# M3406-Board_Match.net
KiCad netlist of a schematic drawn in Altium Designer
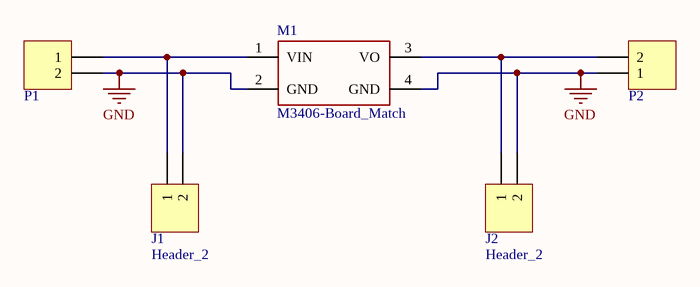
[diagram p0: M3406-Board_Match.SchDoc]

(export (version "E")
  (design (tool "Eeschema 10.0.6"))
  (components
    (comp (ref "J1")
      (value "Header_2")
      (footprint "HDR-TH_2P-P2.54-V-M-1")
      (description "直插,P=2.54mm")
      (libsource (lib "") (part "Header_2_1"))
    )
    (comp (ref "J2")
      (value "Header_2")
      (footprint "HDR-TH_2P-P2.54-V-M-1")
      (description "直插,P=2.54mm")
      (libsource (lib "") (part "Header_2_1"))
    )
    (comp (ref "M1")
      (value "M3406-Board_Match")
      (footprint "M3406-Board_Match")
      (description "M3406匹配板")
      (libsource (lib "std_lib") (part "M3406-Board_Match"))
    )
    (comp (ref "P1")
      (value "KF301-5")
      (footprint "TH_P5.00_KF301-5.0-2P")
      (description "直插,P=2.54mm")
      (libsource (lib "std_lib") (part "Header_2"))
    )
    (comp (ref "P2")
      (value "KF301-5")
      (footprint "TH_P5.00_KF301-5.0-2P")
      (description "直插,P=2.54mm")
      (libsource (lib "") (part "Header_2_2"))
    )
  )
  (nets
    (net (code "1") (name "GND") (class "Default")
      (node (ref "J1") (pin "2") (pinfunction "2_2") (pintype "passive"))
      (node (ref "J2") (pin "2") (pinfunction "2_2") (pintype "passive"))
      (node (ref "M1") (pin "2") (pinfunction "GND_2") (pintype "passive"))
      (node (ref "M1") (pin "4") (pinfunction "GND_4") (pintype "passive"))
      (node (ref "P1") (pin "2") (pinfunction "2_2") (pintype "passive"))
      (node (ref "P2") (pin "1") (pinfunction "1_1") (pintype "passive"))
    )
    (net (code "2") (name "Net-(M1-VIN)") (class "Default")
      (node (ref "J1") (pin "1") (pinfunction "1_1") (pintype "passive"))
      (node (ref "M1") (pin "1") (pinfunction "VIN_1") (pintype "passive"))
      (node (ref "P1") (pin "1") (pinfunction "1_1") (pintype "passive"))
    )
    (net (code "3") (name "Net-(M1-VO)") (class "Default")
      (node (ref "J2") (pin "1") (pinfunction "1_1") (pintype "passive"))
      (node (ref "M1") (pin "3") (pinfunction "VO_3") (pintype "passive"))
      (node (ref "P2") (pin "2") (pinfunction "2_2") (pintype "passive"))
    )
  )
)
